# top5v.net
KiCad netlist of a schematic drawn in EAGLE
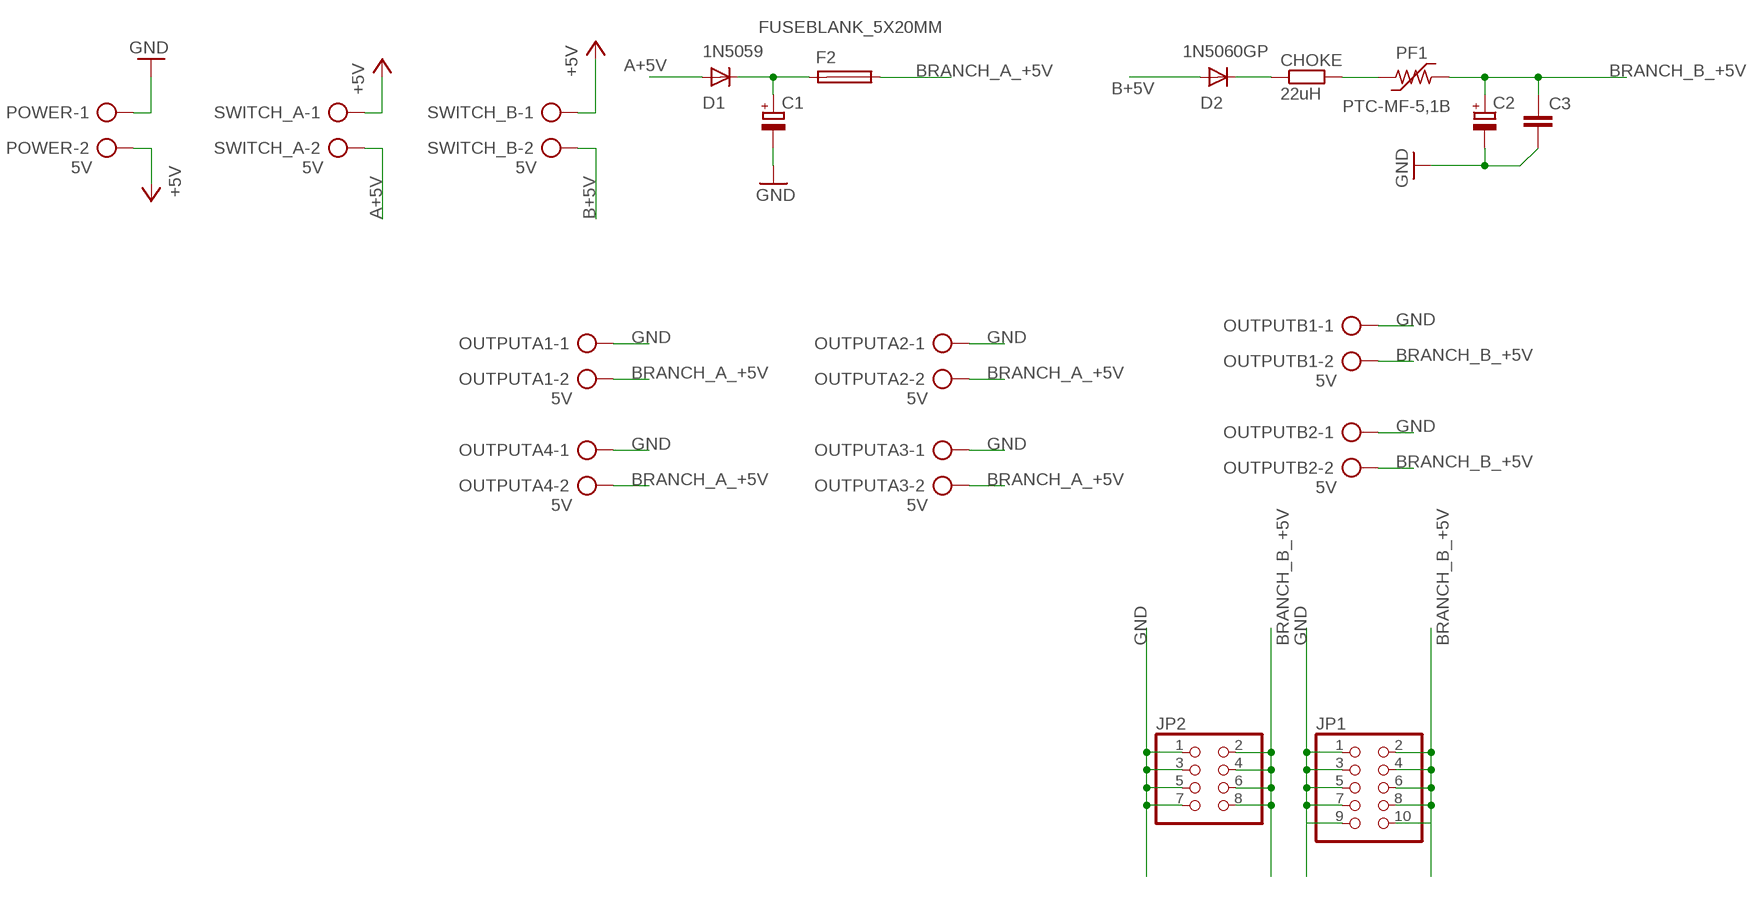
[diagram p0: schematic, sheet 1]

(export (version "E")
  (design (tool "Eeschema 10.0.6"))
  (components
    (comp (ref "C1")
      (value "CPOL-EUE2.5-5")
      (footprint "eagle-import:E2,5-5")
      (libsource (lib "eagle-import") (part "CPOL-EUE2.5-5"))
    )
    (comp (ref "C2")
      (value "CPOL-EUE2.5-5")
      (footprint "eagle-import:E2,5-5")
      (libsource (lib "eagle-import") (part "CPOL-EUE2.5-5"))
    )
    (comp (ref "C3")
      (value "C-EU025-024X044")
      (footprint "eagle-import:C025-024X044")
      (libsource (lib "eagle-import") (part "C-EU025-024X044"))
    )
    (comp (ref "CHOKE")
      (value "22uH")
      (footprint "eagle-import:0411_15")
      (libsource (lib "eagle-import") (part "R-EU_0411_15"))
    )
    (comp (ref "D1")
      (value "1N5059")
      (footprint "eagle-import:DO204-10")
      (libsource (lib "eagle-import") (part "1N5059"))
    )
    (comp (ref "D2")
      (value "1N5060GP")
      (footprint "eagle-import:DO15-12")
      (libsource (lib "eagle-import") (part "1N5060GP"))
    )
    (comp (ref "F2")
      (value "FUSEBLANK_5X20MM")
      (footprint "eagle-import:FUSE_HOLDER_5X20MM")
      (libsource (lib "eagle-import") (part "FUSEBLANK_5X20MM"))
    )
    (comp (ref "JP1")
      (value "PINHD-2X5")
      (footprint "eagle-import:2X05")
      (libsource (lib "eagle-import") (part "PINHD-2X5"))
    )
    (comp (ref "JP2")
      (value "PINHD-2X4")
      (footprint "eagle-import:2X04")
      (libsource (lib "eagle-import") (part "PINHD-2X4"))
    )
    (comp (ref "OUTPUTA1")
      (value "5V")
      (footprint "eagle-import:AK500_2")
      (libsource (lib "eagle-import") (part "AK500/2"))
    )
    (comp (ref "OUTPUTA2")
      (value "5V")
      (footprint "eagle-import:AK500_2")
      (libsource (lib "eagle-import") (part "AK500/2"))
    )
    (comp (ref "OUTPUTA3")
      (value "5V")
      (footprint "eagle-import:AK500_2")
      (libsource (lib "eagle-import") (part "AK500/2"))
    )
    (comp (ref "OUTPUTA4")
      (value "5V")
      (footprint "eagle-import:AK500_2")
      (libsource (lib "eagle-import") (part "AK500/2"))
    )
    (comp (ref "OUTPUTB1")
      (value "5V")
      (footprint "eagle-import:AK500_2")
      (libsource (lib "eagle-import") (part "AK500/2"))
    )
    (comp (ref "OUTPUTB2")
      (value "5V")
      (footprint "eagle-import:AK500_2")
      (libsource (lib "eagle-import") (part "AK500/2"))
    )
    (comp (ref "PF1")
      (value "PTC-MF-5,1B")
      (footprint "eagle-import:MF-5_1B")
      (libsource (lib "eagle-import") (part "PTC-MF-5,1B"))
    )
    (comp (ref "POWER")
      (value "5V")
      (footprint "eagle-import:AK500_2")
      (libsource (lib "eagle-import") (part "AK500/2"))
    )
    (comp (ref "SWITCH_A")
      (value "5V")
      (footprint "eagle-import:AK500_2")
      (libsource (lib "eagle-import") (part "AK500/2"))
    )
    (comp (ref "SWITCH_B")
      (value "5V")
      (footprint "eagle-import:AK500_2")
      (libsource (lib "eagle-import") (part "AK500/2"))
    )
  )
  (nets
    (net (code "1") (name "+5V") (class "Default")
      (node (ref "POWER") (pin "2") (pinfunction "KL_2") (pintype "passive"))
      (node (ref "SWITCH_A") (pin "1") (pinfunction "KL_1") (pintype "passive"))
      (node (ref "SWITCH_B") (pin "1") (pinfunction "KL_1") (pintype "passive"))
    )
    (net (code "2") (name "/A+5V") (class "Default")
      (node (ref "D1") (pin "A") (pinfunction "A_A") (pintype "passive"))
      (node (ref "SWITCH_A") (pin "2") (pinfunction "KL_2") (pintype "passive"))
    )
    (net (code "3") (name "/B+5V") (class "Default")
      (node (ref "D2") (pin "A") (pinfunction "A_A") (pintype "passive"))
      (node (ref "SWITCH_B") (pin "2") (pinfunction "KL_2") (pintype "passive"))
    )
    (net (code "4") (name "/BRANCH_A_+5V") (class "Default")
      (node (ref "F2") (pin "1") (pinfunction "1_1") (pintype "passive"))
      (node (ref "OUTPUTA1") (pin "2") (pinfunction "KL_2") (pintype "passive"))
      (node (ref "OUTPUTA2") (pin "2") (pinfunction "KL_2") (pintype "passive"))
      (node (ref "OUTPUTA3") (pin "2") (pinfunction "KL_2") (pintype "passive"))
      (node (ref "OUTPUTA4") (pin "2") (pinfunction "KL_2") (pintype "passive"))
    )
    (net (code "5") (name "/BRANCH_B_+5V") (class "Default")
      (node (ref "C2") (pin "+") (pinfunction "+_+") (pintype "passive"))
      (node (ref "C3") (pin "1") (pinfunction "1_1") (pintype "passive"))
      (node (ref "JP1") (pin "10") (pinfunction "10_10") (pintype "passive"))
      (node (ref "JP1") (pin "2") (pinfunction "2_2") (pintype "passive"))
      (node (ref "JP1") (pin "4") (pinfunction "4_4") (pintype "passive"))
      (node (ref "JP1") (pin "6") (pinfunction "6_6") (pintype "passive"))
      (node (ref "JP1") (pin "8") (pinfunction "8_8") (pintype "passive"))
      (node (ref "JP2") (pin "2") (pinfunction "2_2") (pintype "passive"))
      (node (ref "JP2") (pin "4") (pinfunction "4_4") (pintype "passive"))
      (node (ref "JP2") (pin "6") (pinfunction "6_6") (pintype "passive"))
      (node (ref "JP2") (pin "8") (pinfunction "8_8") (pintype "passive"))
      (node (ref "OUTPUTB1") (pin "2") (pinfunction "KL_2") (pintype "passive"))
      (node (ref "OUTPUTB2") (pin "2") (pinfunction "KL_2") (pintype "passive"))
      (node (ref "PF1") (pin "2") (pinfunction "2_2") (pintype "passive"))
    )
    (net (code "6") (name "GND") (class "Default")
      (node (ref "C1") (pin "-") (pinfunction "-_-") (pintype "passive"))
      (node (ref "C2") (pin "-") (pinfunction "-_-") (pintype "passive"))
      (node (ref "C3") (pin "2") (pinfunction "2_2") (pintype "passive"))
      (node (ref "JP1") (pin "1") (pinfunction "1_1") (pintype "passive"))
      (node (ref "JP1") (pin "3") (pinfunction "3_3") (pintype "passive"))
      (node (ref "JP1") (pin "5") (pinfunction "5_5") (pintype "passive"))
      (node (ref "JP1") (pin "7") (pinfunction "7_7") (pintype "passive"))
      (node (ref "JP1") (pin "9") (pinfunction "9_9") (pintype "passive"))
      (node (ref "JP2") (pin "1") (pinfunction "1_1") (pintype "passive"))
      (node (ref "JP2") (pin "3") (pinfunction "3_3") (pintype "passive"))
      (node (ref "JP2") (pin "5") (pinfunction "5_5") (pintype "passive"))
      (node (ref "JP2") (pin "7") (pinfunction "7_7") (pintype "passive"))
      (node (ref "OUTPUTA1") (pin "1") (pinfunction "KL_1") (pintype "passive"))
      (node (ref "OUTPUTA2") (pin "1") (pinfunction "KL_1") (pintype "passive"))
      (node (ref "OUTPUTA3") (pin "1") (pinfunction "KL_1") (pintype "passive"))
      (node (ref "OUTPUTA4") (pin "1") (pinfunction "KL_1") (pintype "passive"))
      (node (ref "OUTPUTB1") (pin "1") (pinfunction "KL_1") (pintype "passive"))
      (node (ref "OUTPUTB2") (pin "1") (pinfunction "KL_1") (pintype "passive"))
      (node (ref "POWER") (pin "1") (pinfunction "KL_1") (pintype "passive"))
    )
    (net (code "7") (name "Net-(C1-Pad+)") (class "Default")
      (node (ref "C1") (pin "+") (pinfunction "+_+") (pintype "passive"))
      (node (ref "D1") (pin "C") (pinfunction "C_C") (pintype "passive"))
      (node (ref "F2") (pin "2") (pinfunction "2_2") (pintype "passive"))
    )
    (net (code "8") (name "Net-(CHOKE-Pad1)") (class "Default")
      (node (ref "CHOKE") (pin "1") (pinfunction "1_1") (pintype "passive"))
      (node (ref "D2") (pin "C") (pinfunction "C_C") (pintype "passive"))
    )
    (net (code "9") (name "Net-(CHOKE-Pad2)") (class "Default")
      (node (ref "CHOKE") (pin "2") (pinfunction "2_2") (pintype "passive"))
      (node (ref "PF1") (pin "1") (pinfunction "1_1") (pintype "passive"))
    )
  )
)
